# Add4andGain.net
KiCad netlist of a schematic drawn in EAGLE
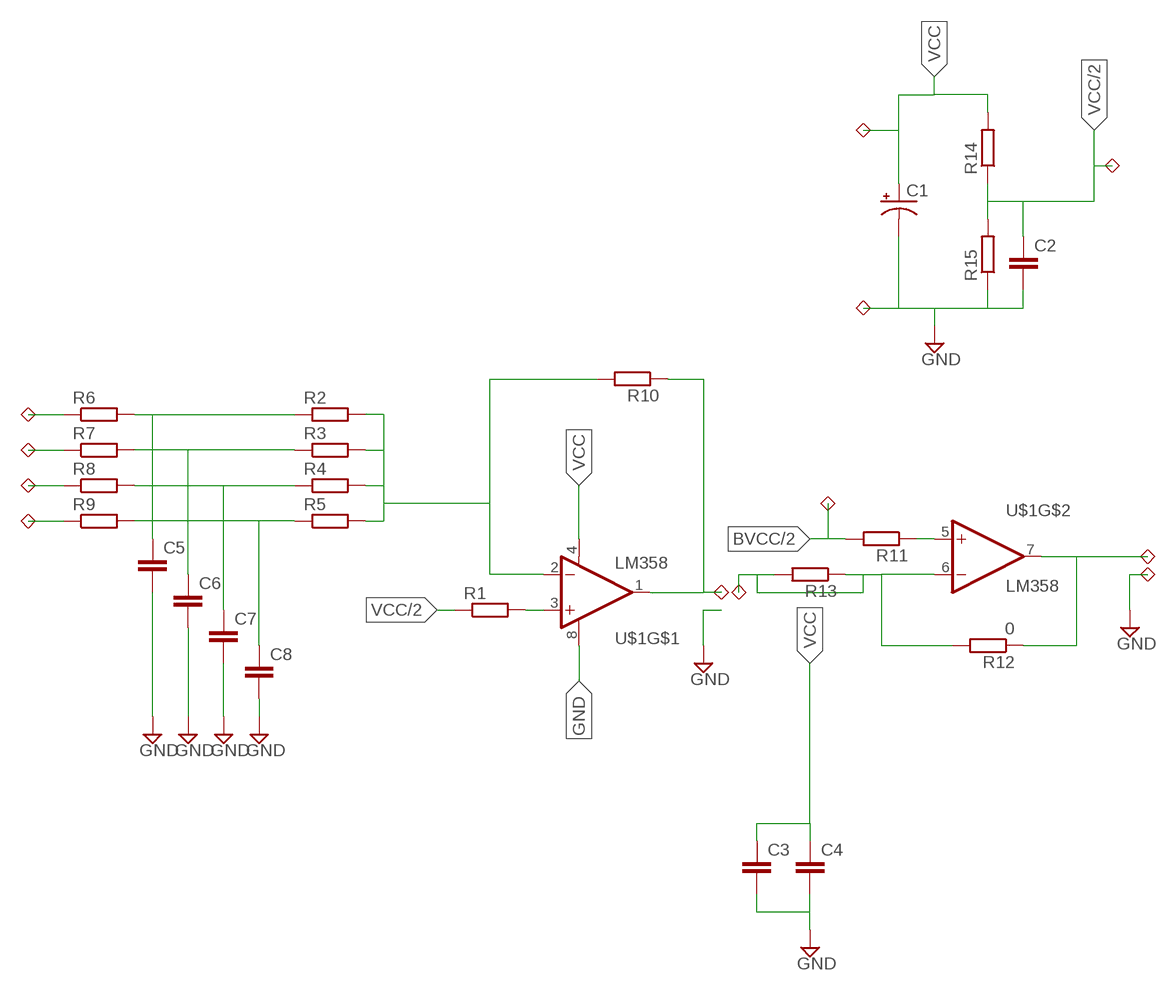
[diagram p0: schematic, sheet 1]

(export (version "E")
  (design (tool "Eeschema 10.0.6"))
  (components
    (comp (ref "C1")
      (value "CPOL-USSMCE")
      (footprint "eagle-import:SMC_E")
      (libsource (lib "eagle-import") (part "CPOL-USSMCE"))
    )
    (comp (ref "C2")
      (value "C-EUC0805")
      (footprint "eagle-import:C0805")
      (libsource (lib "eagle-import") (part "C-EUC0805"))
    )
    (comp (ref "C3")
      (value "C-EUC0805")
      (footprint "eagle-import:C0805")
      (libsource (lib "eagle-import") (part "C-EUC0805"))
    )
    (comp (ref "C4")
      (value "C-EUC0805")
      (footprint "eagle-import:C0805")
      (libsource (lib "eagle-import") (part "C-EUC0805"))
    )
    (comp (ref "C5")
      (value "C-EUC0805")
      (footprint "eagle-import:C0805")
      (libsource (lib "eagle-import") (part "C-EUC0805"))
    )
    (comp (ref "C6")
      (value "C-EUC0805")
      (footprint "eagle-import:C0805")
      (libsource (lib "eagle-import") (part "C-EUC0805"))
    )
    (comp (ref "C7")
      (value "C-EUC0805")
      (footprint "eagle-import:C0805")
      (libsource (lib "eagle-import") (part "C-EUC0805"))
    )
    (comp (ref "C8")
      (value "C-EUC0805")
      (footprint "eagle-import:C0805")
      (libsource (lib "eagle-import") (part "C-EUC0805"))
    )
    (comp (ref "R1")
      (value "R-EU_R0603")
      (footprint "eagle-import:R0603")
      (libsource (lib "eagle-import") (part "R-EU_R0603"))
    )
    (comp (ref "R2")
      (value "R-EU_R0603")
      (footprint "eagle-import:R0603")
      (libsource (lib "eagle-import") (part "R-EU_R0603"))
    )
    (comp (ref "R3")
      (value "R-EU_R0603")
      (footprint "eagle-import:R0603")
      (libsource (lib "eagle-import") (part "R-EU_R0603"))
    )
    (comp (ref "R4")
      (value "R-EU_R0603")
      (footprint "eagle-import:R0603")
      (libsource (lib "eagle-import") (part "R-EU_R0603"))
    )
    (comp (ref "R5")
      (value "R-EU_R0603")
      (footprint "eagle-import:R0603")
      (libsource (lib "eagle-import") (part "R-EU_R0603"))
    )
    (comp (ref "R6")
      (value "R-EU_R0603")
      (footprint "eagle-import:R0603")
      (libsource (lib "eagle-import") (part "R-EU_R0603"))
    )
    (comp (ref "R7")
      (value "R-EU_R0603")
      (footprint "eagle-import:R0603")
      (libsource (lib "eagle-import") (part "R-EU_R0603"))
    )
    (comp (ref "R8")
      (value "R-EU_R0603")
      (footprint "eagle-import:R0603")
      (libsource (lib "eagle-import") (part "R-EU_R0603"))
    )
    (comp (ref "R9")
      (value "R-EU_R0603")
      (footprint "eagle-import:R0603")
      (libsource (lib "eagle-import") (part "R-EU_R0603"))
    )
    (comp (ref "R10")
      (value "R-EU_R0603")
      (footprint "eagle-import:R0603")
      (libsource (lib "eagle-import") (part "R-EU_R0603"))
    )
    (comp (ref "R11")
      (value "R-EU_R0603")
      (footprint "eagle-import:R0603")
      (libsource (lib "eagle-import") (part "R-EU_R0603"))
    )
    (comp (ref "R12")
      (value "0")
      (footprint "eagle-import:R0603")
      (libsource (lib "eagle-import") (part "R-EU_R0603"))
    )
    (comp (ref "R13")
      (value "R-EU_R0603")
      (footprint "eagle-import:R0603")
      (libsource (lib "eagle-import") (part "R-EU_R0603"))
    )
    (comp (ref "R14")
      (value "R-EU_R0603")
      (footprint "eagle-import:R0603")
      (libsource (lib "eagle-import") (part "R-EU_R0603"))
    )
    (comp (ref "R15")
      (value "R-EU_R0603")
      (footprint "eagle-import:R0603")
      (libsource (lib "eagle-import") (part "R-EU_R0603"))
    )
    (comp (ref "U$1")
      (value "LM358")
      (footprint "eagle-import:SO08")
      (libsource (lib "eagle-import") (part "LM358"))
    )
    (comp (ref "U$2")
      (value "1PIN_SM")
      (footprint "eagle-import:THUMBNAIL_SM")
      (libsource (lib "eagle-import") (part "1PIN_SM"))
    )
    (comp (ref "U$3")
      (value "1PIN_SM")
      (footprint "eagle-import:THUMBNAIL_SM")
      (libsource (lib "eagle-import") (part "1PIN_SM"))
    )
    (comp (ref "U$4")
      (value "1PIN_SM")
      (footprint "eagle-import:THUMBNAIL_SM")
      (libsource (lib "eagle-import") (part "1PIN_SM"))
    )
    (comp (ref "U$5")
      (value "1PIN_SM")
      (footprint "eagle-import:THUMBNAIL_SM")
      (libsource (lib "eagle-import") (part "1PIN_SM"))
    )
    (comp (ref "U$6")
      (value "1PIN_SM")
      (footprint "eagle-import:THUMBNAIL_SM")
      (libsource (lib "eagle-import") (part "1PIN_SM"))
    )
    (comp (ref "U$7")
      (value "1PIN_SM")
      (footprint "eagle-import:THUMBNAIL_SM")
      (libsource (lib "eagle-import") (part "1PIN_SM"))
    )
    (comp (ref "U$8")
      (value "1PIN_SM")
      (footprint "eagle-import:THUMBNAIL_SM")
      (libsource (lib "eagle-import") (part "1PIN_SM"))
    )
    (comp (ref "U$9")
      (value "1PIN_SM")
      (footprint "eagle-import:THUMBNAIL_SM")
      (libsource (lib "eagle-import") (part "1PIN_SM"))
    )
    (comp (ref "U$10")
      (value "1PIN_SM")
      (footprint "eagle-import:THUMBNAIL_SM")
      (libsource (lib "eagle-import") (part "1PIN_SM"))
    )
    (comp (ref "U$12")
      (value "1PIN_SM")
      (footprint "eagle-import:THUMBNAIL_SM")
      (libsource (lib "eagle-import") (part "1PIN_SM"))
    )
    (comp (ref "U$15")
      (value "1PIN_SM")
      (footprint "eagle-import:THUMBNAIL_SM")
      (libsource (lib "eagle-import") (part "1PIN_SM"))
    )
    (comp (ref "U$16")
      (value "1PIN_SM")
      (footprint "eagle-import:THUMBNAIL_SM")
      (libsource (lib "eagle-import") (part "1PIN_SM"))
    )
  )
  (nets
    (net (code "1") (name "BVCC{slash}2") (class "Default")
      (node (ref "R11") (pin "2") (pinfunction "2_2") (pintype "passive"))
      (node (ref "U$6") (pin "P$1") (pinfunction "P$1_P$1") (pintype "bidirectional"))
    )
    (net (code "2") (name "GND") (class "Default")
      (node (ref "C1") (pin "-") (pinfunction "-_-") (pintype "passive"))
      (node (ref "C2") (pin "2") (pinfunction "2_2") (pintype "passive"))
      (node (ref "C3") (pin "2") (pinfunction "2_2") (pintype "passive"))
      (node (ref "C4") (pin "2") (pinfunction "2_2") (pintype "passive"))
      (node (ref "C5") (pin "2") (pinfunction "2_2") (pintype "passive"))
      (node (ref "C6") (pin "2") (pinfunction "2_2") (pintype "passive"))
      (node (ref "C7") (pin "2") (pinfunction "2_2") (pintype "passive"))
      (node (ref "C8") (pin "2") (pinfunction "2_2") (pintype "passive"))
      (node (ref "R15") (pin "1") (pinfunction "1_1") (pintype "passive"))
      (node (ref "U$1") (pin "8") (pinfunction "V+_8") (pintype "power_in"))
      (node (ref "U$16") (pin "P$1") (pinfunction "P$1_P$1") (pintype "bidirectional"))
      (node (ref "U$7") (pin "P$1") (pinfunction "P$1_P$1") (pintype "bidirectional"))
    )
    (net (code "3") (name "Net-(C5-Pad1)") (class "Default")
      (node (ref "C5") (pin "1") (pinfunction "1_1") (pintype "passive"))
      (node (ref "R2") (pin "1") (pinfunction "1_1") (pintype "passive"))
      (node (ref "R6") (pin "2") (pinfunction "2_2") (pintype "passive"))
    )
    (net (code "4") (name "Net-(C6-Pad1)") (class "Default")
      (node (ref "C6") (pin "1") (pinfunction "1_1") (pintype "passive"))
      (node (ref "R3") (pin "1") (pinfunction "1_1") (pintype "passive"))
      (node (ref "R7") (pin "2") (pinfunction "2_2") (pintype "passive"))
    )
    (net (code "5") (name "Net-(C7-Pad1)") (class "Default")
      (node (ref "C7") (pin "1") (pinfunction "1_1") (pintype "passive"))
      (node (ref "R4") (pin "1") (pinfunction "1_1") (pintype "passive"))
      (node (ref "R8") (pin "2") (pinfunction "2_2") (pintype "passive"))
    )
    (net (code "6") (name "Net-(C8-Pad1)") (class "Default")
      (node (ref "C8") (pin "1") (pinfunction "1_1") (pintype "passive"))
      (node (ref "R5") (pin "1") (pinfunction "1_1") (pintype "passive"))
      (node (ref "R9") (pin "2") (pinfunction "2_2") (pintype "passive"))
    )
    (net (code "7") (name "Net-(R6-Pad1)") (class "Default")
      (node (ref "R6") (pin "1") (pinfunction "1_1") (pintype "passive"))
      (node (ref "U$2") (pin "P$1") (pinfunction "P$1_P$1") (pintype "bidirectional"))
    )
    (net (code "8") (name "Net-(R7-Pad1)") (class "Default")
      (node (ref "R7") (pin "1") (pinfunction "1_1") (pintype "passive"))
      (node (ref "U$3") (pin "P$1") (pinfunction "P$1_P$1") (pintype "bidirectional"))
    )
    (net (code "9") (name "Net-(R8-Pad1)") (class "Default")
      (node (ref "R8") (pin "1") (pinfunction "1_1") (pintype "passive"))
      (node (ref "U$4") (pin "P$1") (pinfunction "P$1_P$1") (pintype "bidirectional"))
    )
    (net (code "10") (name "Net-(R9-Pad1)") (class "Default")
      (node (ref "R9") (pin "1") (pinfunction "1_1") (pintype "passive"))
      (node (ref "U$5") (pin "P$1") (pinfunction "P$1_P$1") (pintype "bidirectional"))
    )
    (net (code "11") (name "Net-(U$1A-+IN)") (class "Default")
      (node (ref "R1") (pin "2") (pinfunction "2_2") (pintype "passive"))
      (node (ref "U$1") (pin "3") (pinfunction "+IN_3") (pintype "input"))
    )
    (net (code "12") (name "Net-(U$1A--IN)") (class "Default")
      (node (ref "R10") (pin "2") (pinfunction "2_2") (pintype "passive"))
      (node (ref "R2") (pin "2") (pinfunction "2_2") (pintype "passive"))
      (node (ref "R3") (pin "2") (pinfunction "2_2") (pintype "passive"))
      (node (ref "R4") (pin "2") (pinfunction "2_2") (pintype "passive"))
      (node (ref "R5") (pin "2") (pinfunction "2_2") (pintype "passive"))
      (node (ref "U$1") (pin "2") (pinfunction "-IN_2") (pintype "input"))
    )
    (net (code "13") (name "Net-(U$1A-OUT)") (class "Default")
      (node (ref "R10") (pin "1") (pinfunction "1_1") (pintype "passive"))
      (node (ref "U$1") (pin "1") (pinfunction "OUT_1") (pintype "output"))
      (node (ref "U$8") (pin "P$1") (pinfunction "P$1_P$1") (pintype "bidirectional"))
    )
    (net (code "14") (name "Net-(U$1B-+IN)") (class "Default")
      (node (ref "R11") (pin "1") (pinfunction "1_1") (pintype "passive"))
      (node (ref "U$1") (pin "5") (pinfunction "+IN_5") (pintype "input"))
    )
    (net (code "15") (name "Net-(U$1B--IN)") (class "Default")
      (node (ref "R12") (pin "2") (pinfunction "2_2") (pintype "passive"))
      (node (ref "R13") (pin "1") (pinfunction "1_1") (pintype "passive"))
      (node (ref "R13") (pin "2") (pinfunction "2_2") (pintype "passive"))
      (node (ref "U$1") (pin "6") (pinfunction "-IN_6") (pintype "input"))
      (node (ref "U$9") (pin "P$1") (pinfunction "P$1_P$1") (pintype "bidirectional"))
    )
    (net (code "16") (name "Net-(U$1B-OUT)") (class "Default")
      (node (ref "R12") (pin "1") (pinfunction "1_1") (pintype "passive"))
      (node (ref "U$1") (pin "7") (pinfunction "OUT_7") (pintype "output"))
      (node (ref "U$15") (pin "P$1") (pinfunction "P$1_P$1") (pintype "bidirectional"))
    )
    (net (code "17") (name "VCC") (class "Default")
      (node (ref "C1") (pin "+") (pinfunction "+_+") (pintype "passive"))
      (node (ref "C3") (pin "1") (pinfunction "1_1") (pintype "passive"))
      (node (ref "C4") (pin "1") (pinfunction "1_1") (pintype "passive"))
      (node (ref "R14") (pin "2") (pinfunction "2_2") (pintype "passive"))
      (node (ref "U$1") (pin "4") (pinfunction "V-_4") (pintype "power_in"))
      (node (ref "U$12") (pin "P$1") (pinfunction "P$1_P$1") (pintype "bidirectional"))
    )
    (net (code "18") (name "VCC{slash}2") (class "Default")
      (node (ref "C2") (pin "1") (pinfunction "1_1") (pintype "passive"))
      (node (ref "R1") (pin "1") (pinfunction "1_1") (pintype "passive"))
      (node (ref "R14") (pin "1") (pinfunction "1_1") (pintype "passive"))
      (node (ref "R15") (pin "2") (pinfunction "2_2") (pintype "passive"))
      (node (ref "U$10") (pin "P$1") (pinfunction "P$1_P$1") (pintype "bidirectional"))
    )
  )
)
